# battery_monitor_6803-2_Rev6.net
KiCad netlist of a schematic drawn in EAGLE
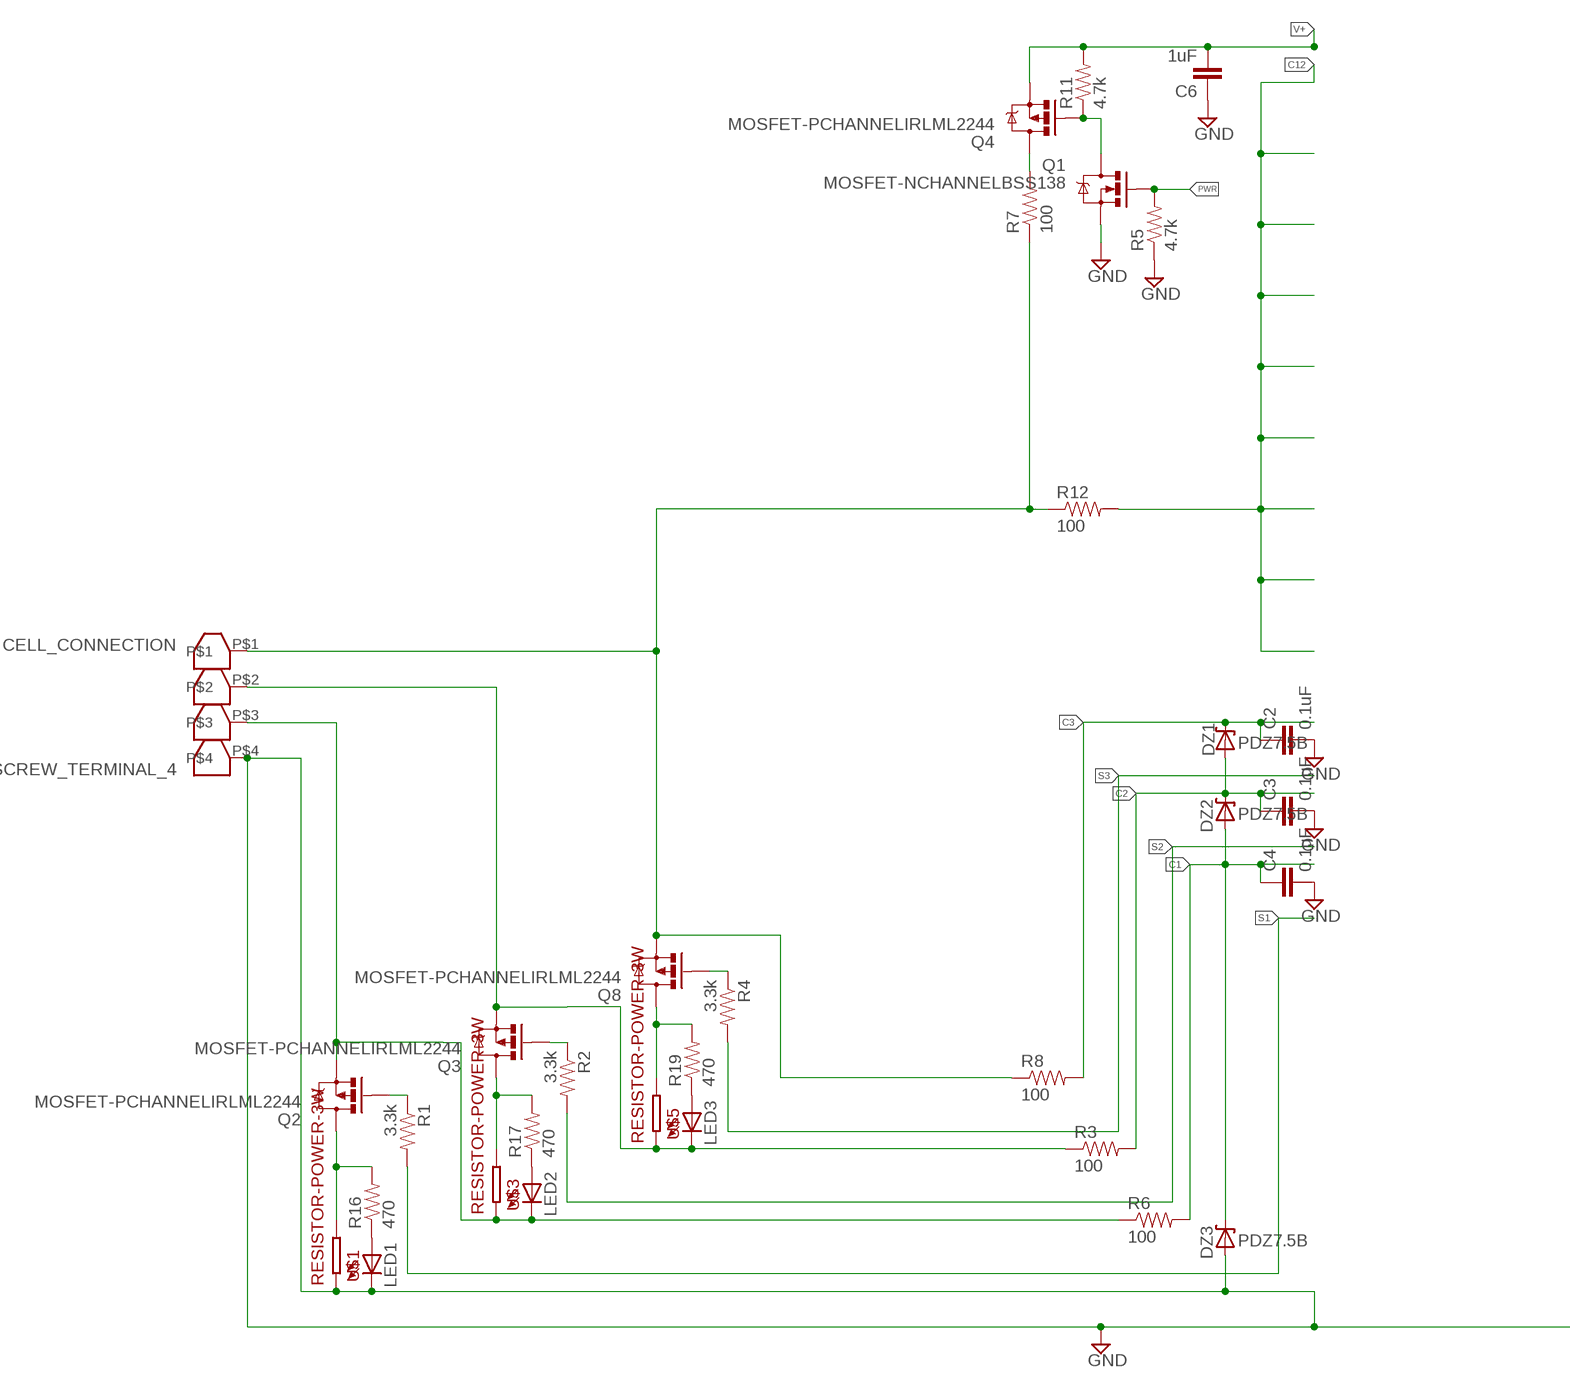
[diagram p0: schematic, sheet 1, part 1 of 2]
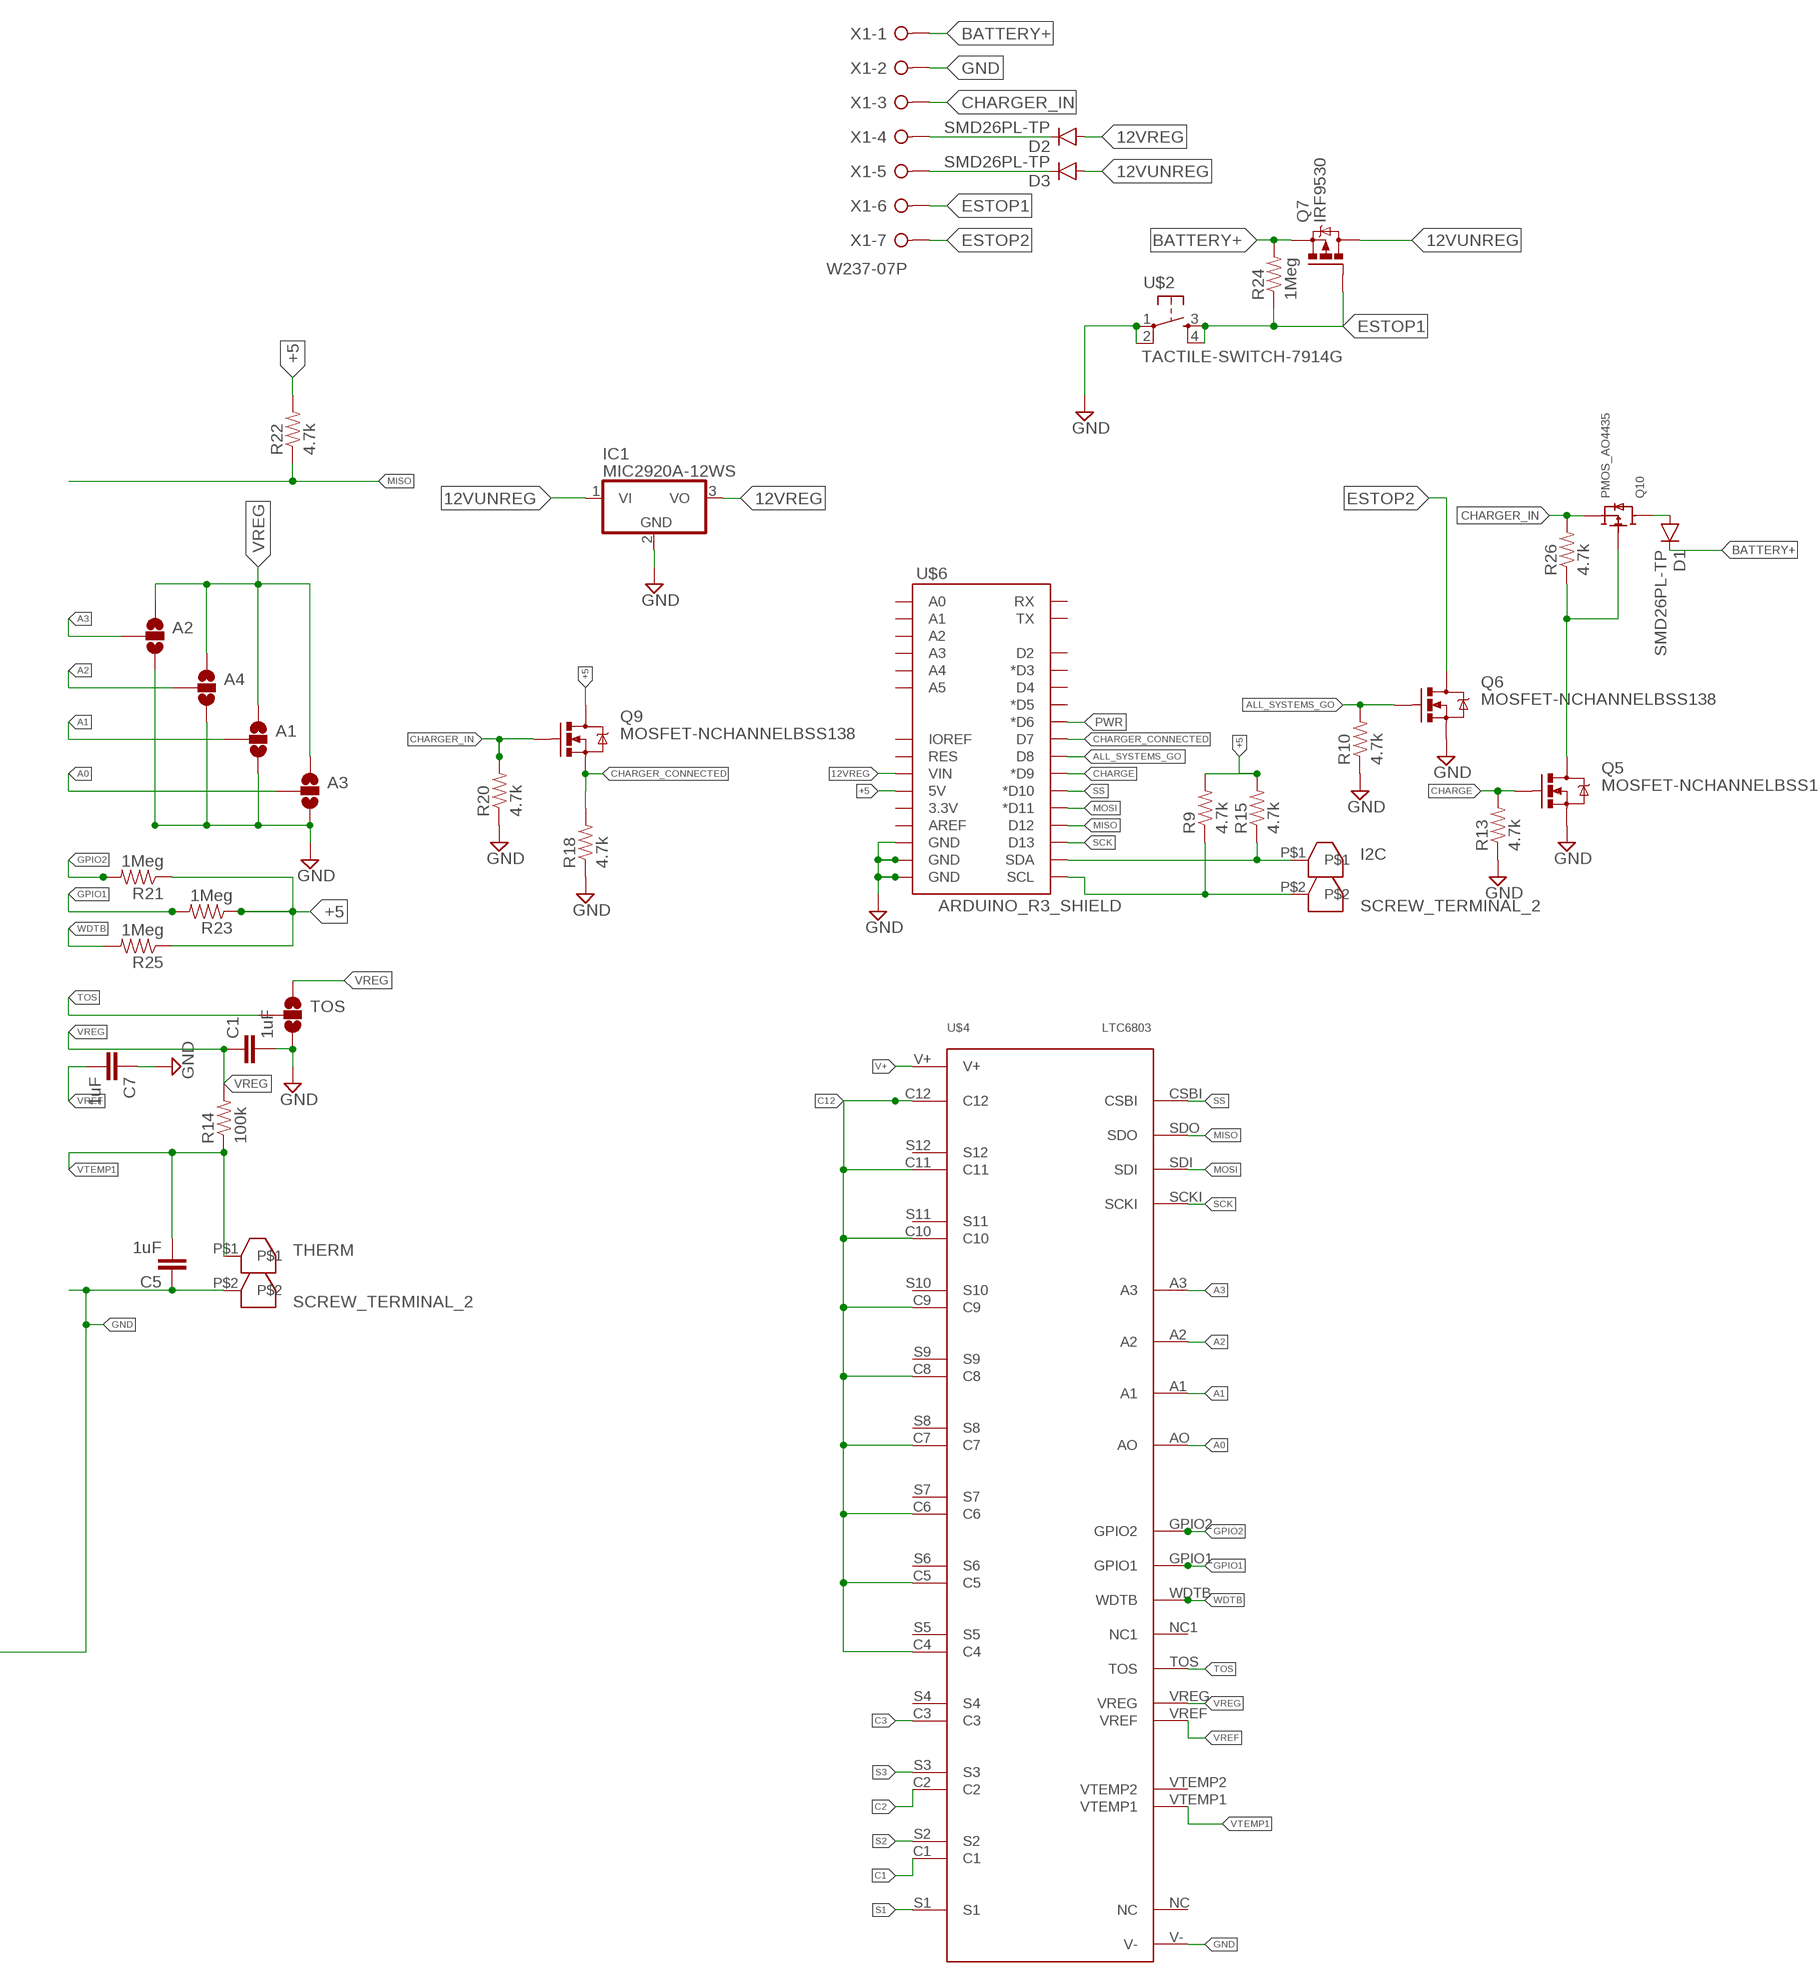
[diagram p1: schematic, sheet 1, part 2 of 2]

(export (version "E")
  (design (tool "Eeschema 10.0.6"))
  (components
    (comp (ref "A1")
      (value "SOLDERJUMPER_2WAYS")
      (footprint "eagle-import:SJ_3")
      (libsource (lib "eagle-import") (part "SOLDERJUMPER_2WAYS"))
    )
    (comp (ref "A2")
      (value "SOLDERJUMPER_2WAYS")
      (footprint "eagle-import:SJ_3")
      (libsource (lib "eagle-import") (part "SOLDERJUMPER_2WAYS"))
    )
    (comp (ref "A3")
      (value "SOLDERJUMPER_2WAYS")
      (footprint "eagle-import:SJ_3")
      (libsource (lib "eagle-import") (part "SOLDERJUMPER_2WAYS"))
    )
    (comp (ref "A4")
      (value "SOLDERJUMPER_2WAYS")
      (footprint "eagle-import:SJ_3")
      (libsource (lib "eagle-import") (part "SOLDERJUMPER_2WAYS"))
    )
    (comp (ref "C1")
      (value "1uF")
      (footprint "eagle-import:0603-CAP")
      (fields (field (name "MPN") "C0603X5R0J105M030BC") (field (name "PROD_ID") "CAP-08390"))
      (libsource (lib "eagle-import") (part "0.1UF-100V-10%(0603)"))
    )
    (comp (ref "C2")
      (value "0.1uF")
      (footprint "eagle-import:0603-CAP")
      (fields (field (name "MF") "AVX CORPORATION") (field (name "MPN") "0603YG104ZAT2A"))
      (libsource (lib "eagle-import") (part "0.1UF-100V-10%(0603)"))
    )
    (comp (ref "C3")
      (value "0.1uF")
      (footprint "eagle-import:0603-CAP")
      (fields (field (name "MF") "AVX CORPORATION") (field (name "MPN") "0603YG104ZAT2A"))
      (libsource (lib "eagle-import") (part "0.1UF-100V-10%(0603)"))
    )
    (comp (ref "C4")
      (value "0.1uF")
      (footprint "eagle-import:0603-CAP")
      (fields (field (name "MF") "AVX CORPORATION") (field (name "MPN") "0603YG104ZAT2A"))
      (libsource (lib "eagle-import") (part "0.1UF-100V-10%(0603)"))
    )
    (comp (ref "C5")
      (value "1uF")
      (footprint "eagle-import:0603-CAP")
      (fields (field (name "MPN") "C0603X5R0J105M030BC") (field (name "PROD_ID") "CAP-08390"))
      (libsource (lib "eagle-import") (part "0.1UF-100V-10%(0603)"))
    )
    (comp (ref "C6")
      (value "1uF")
      (footprint "eagle-import:0603-CAP")
      (fields (field (name "MPN") "C0603X5R0J105M030BC") (field (name "PROD_ID") "CAP-08390"))
      (libsource (lib "eagle-import") (part "0.1UF-100V-10%(0603)"))
    )
    (comp (ref "C7")
      (value "1uF")
      (footprint "eagle-import:0603-CAP")
      (fields (field (name "MPN") "C0603X5R0J105M030BC") (field (name "PROD_ID") "CAP-08390"))
      (libsource (lib "eagle-import") (part "0.1UF-100V-10%(0603)"))
    )
    (comp (ref "CELL_CONNECTION")
      (value "SCREW_TERMINAL_4")
      (footprint "eagle-import:SCREW_TERMINAL_4")
      (fields (field (name "MF") "TYCO ELECTRONICS") (field (name "MPN") "282834-4"))
      (libsource (lib "eagle-import") (part "SCREW_TERMINAL_4"))
    )
    (comp (ref "D1")
      (value "SMD26PL-TP")
      (footprint "eagle-import:SOD-123")
      (libsource (lib "eagle-import") (part "DIODESOD123"))
    )
    (comp (ref "D2")
      (value "SMD26PL-TP")
      (footprint "eagle-import:SOD-123")
      (libsource (lib "eagle-import") (part "DIODESOD123"))
    )
    (comp (ref "D3")
      (value "SMD26PL-TP")
      (footprint "eagle-import:SOD-123")
      (libsource (lib "eagle-import") (part "DIODESOD123"))
    )
    (comp (ref "DZ1")
      (value "PDZ7.5B")
      (footprint "eagle-import:SOD-323@1")
      (fields (field (name "MPN") "PDZ7.5B,115"))
      (libsource (lib "eagle-import") (part "DIODE-ZENER-BZT52"))
    )
    (comp (ref "DZ2")
      (value "PDZ7.5B")
      (footprint "eagle-import:SOD-323@1")
      (fields (field (name "MPN") "PDZ7.5B,115"))
      (libsource (lib "eagle-import") (part "DIODE-ZENER-BZT52"))
    )
    (comp (ref "DZ3")
      (value "PDZ7.5B")
      (footprint "eagle-import:SOD-323@1")
      (fields (field (name "MPN") "PDZ7.5B,115"))
      (libsource (lib "eagle-import") (part "DIODE-ZENER-BZT52"))
    )
    (comp (ref "I2C")
      (value "SCREW_TERMINAL_2")
      (footprint "eagle-import:SCREW_TERMINAL_2")
      (fields (field (name "MF") "TYCO ELECTRONICS") (field (name "MPN") "282834-2"))
      (libsource (lib "eagle-import") (part "SCREW_TERMINAL_2"))
    )
    (comp (ref "IC1")
      (value "MIC2920A-12WS")
      (footprint "eagle-import:SOT223")
      (libsource (lib "eagle-import") (part "MCP1703DB"))
    )
    (comp (ref "LED1")
      (value "LED0603")
      (footprint "eagle-import:LED-0603")
      (fields (field (name "MPN") "150060RS75000"))
      (libsource (lib "eagle-import") (part "LED0603"))
    )
    (comp (ref "LED2")
      (value "LED0603")
      (footprint "eagle-import:LED-0603")
      (fields (field (name "MPN") "150060RS75000"))
      (libsource (lib "eagle-import") (part "LED0603"))
    )
    (comp (ref "LED3")
      (value "LED0603")
      (footprint "eagle-import:LED-0603")
      (fields (field (name "MPN") "150060RS75000"))
      (libsource (lib "eagle-import") (part "LED0603"))
    )
    (comp (ref "Q1")
      (value "MOSFET-NCHANNELBSS138")
      (footprint "eagle-import:SOT23")
      (fields (field (name "MPN") "IRLML0030TRPBF"))
      (libsource (lib "eagle-import") (part "MOSFET-NCHANNELBSS138"))
    )
    (comp (ref "Q2")
      (value "MOSFET-PCHANNELIRLML2244")
      (footprint "eagle-import:SOT23-3@1")
      (fields (field (name "MPN") "IRLML2244TRPBF"))
      (libsource (lib "eagle-import") (part "MOSFET-PCHANNELIRLML2244"))
    )
    (comp (ref "Q3")
      (value "MOSFET-PCHANNELIRLML2244")
      (footprint "eagle-import:SOT23-3@1")
      (fields (field (name "MPN") "IRLML2244TRPBF"))
      (libsource (lib "eagle-import") (part "MOSFET-PCHANNELIRLML2244"))
    )
    (comp (ref "Q4")
      (value "MOSFET-PCHANNELIRLML2244")
      (footprint "eagle-import:SOT23-3@1")
      (fields (field (name "MPN") "IRLML2244TRPBF"))
      (libsource (lib "eagle-import") (part "MOSFET-PCHANNELIRLML2244"))
    )
    (comp (ref "Q5")
      (value "MOSFET-NCHANNELBSS138")
      (footprint "eagle-import:SOT23")
      (fields (field (name "MPN") "IRLML0030TRPBF"))
      (libsource (lib "eagle-import") (part "MOSFET-NCHANNELBSS138"))
    )
    (comp (ref "Q6")
      (value "MOSFET-NCHANNELBSS138")
      (footprint "eagle-import:SOT23")
      (fields (field (name "MPN") "IRLML0030TRPBF"))
      (libsource (lib "eagle-import") (part "MOSFET-NCHANNELBSS138"))
    )
    (comp (ref "Q7")
      (value "IRF9530")
      (footprint "eagle-import:TO220BV")
      (fields (field (name "MPN") "NTE2383"))
      (libsource (lib "eagle-import") (part "IRF9530"))
    )
    (comp (ref "Q8")
      (value "MOSFET-PCHANNELIRLML2244")
      (footprint "eagle-import:SOT23-3@1")
      (fields (field (name "MPN") "IRLML2244TRPBF"))
      (libsource (lib "eagle-import") (part "MOSFET-PCHANNELIRLML2244"))
    )
    (comp (ref "Q9")
      (value "MOSFET-NCHANNELBSS138")
      (footprint "eagle-import:SOT23")
      (fields (field (name "MPN") "IRLML0030TRPBF") (field (name "PROD_ID") "TRANS-00830"))
      (libsource (lib "eagle-import") (part "MOSFET-NCHANNELBSS138"))
    )
    (comp (ref "Q10")
      (value "PMOS_AO4435")
      (footprint "eagle-import:SOIC8")
      (fields (field (name "MPN") "SI9407BDY-T1-GE3"))
      (libsource (lib "eagle-import") (part "PMOS_AO4435"))
    )
    (comp (ref "R1")
      (value "3.3k")
      (footprint "eagle-import:0603-RES")
      (fields (field (name "MF") "VISHAY/DALE") (field (name "MPN") "CRCW06033K00FKEA"))
      (libsource (lib "eagle-import") (part "3.3KOHM1/10W1%(0603)"))
    )
    (comp (ref "R2")
      (value "3.3k")
      (footprint "eagle-import:0603-RES")
      (fields (field (name "MF") "VISHAY/DALE") (field (name "MPN") "CRCW06033K00FKEA"))
      (libsource (lib "eagle-import") (part "3.3KOHM1/10W1%(0603)"))
    )
    (comp (ref "R3")
      (value "100")
      (footprint "eagle-import:0603-RES")
      (fields (field (name "MPN") "ERJ-1GNF1000C"))
      (libsource (lib "eagle-import") (part "3.3KOHM1/10W1%(0603)"))
    )
    (comp (ref "R4")
      (value "3.3k")
      (footprint "eagle-import:0603-RES")
      (fields (field (name "MF") "VISHAY/DALE") (field (name "MPN") "CRCW06033K00FKEA"))
      (libsource (lib "eagle-import") (part "3.3KOHM1/10W1%(0603)"))
    )
    (comp (ref "R5")
      (value "4.7k")
      (footprint "eagle-import:0603-RES")
      (fields (field (name "MF") "VISHAY/DALE") (field (name "MPN") "CRCW06034K70FKEA"))
      (libsource (lib "eagle-import") (part "3.3KOHM1/10W1%(0603)"))
    )
    (comp (ref "R6")
      (value "100")
      (footprint "eagle-import:0603-RES")
      (fields (field (name "MPN") "ERJ-1GNF1000C"))
      (libsource (lib "eagle-import") (part "3.3KOHM1/10W1%(0603)"))
    )
    (comp (ref "R7")
      (value "100")
      (footprint "eagle-import:0603-RES")
      (fields (field (name "MPN") "ERJ-1GNF1000C"))
      (libsource (lib "eagle-import") (part "3.3KOHM1/10W1%(0603)"))
    )
    (comp (ref "R8")
      (value "100")
      (footprint "eagle-import:0603-RES")
      (fields (field (name "MPN") "ERJ-1GNF1000C"))
      (libsource (lib "eagle-import") (part "3.3KOHM1/10W1%(0603)"))
    )
    (comp (ref "R9")
      (value "4.7k")
      (footprint "eagle-import:0603-RES")
      (fields (field (name "MF") "VISHAY/DALE") (field (name "MPN") "CRCW06034K70FKEA"))
      (libsource (lib "eagle-import") (part "3.3KOHM1/10W1%(0603)"))
    )
    (comp (ref "R10")
      (value "4.7k")
      (footprint "eagle-import:0603-RES")
      (fields (field (name "MF") "VISHAY/DALE") (field (name "MPN") "CRCW06034K70FKEA"))
      (libsource (lib "eagle-import") (part "3.3KOHM1/10W1%(0603)"))
    )
    (comp (ref "R11")
      (value "4.7k")
      (footprint "eagle-import:0603-RES")
      (fields (field (name "MF") "VISHAY/DALE") (field (name "MPN") "CRCW06034K70FKEA"))
      (libsource (lib "eagle-import") (part "3.3KOHM1/10W1%(0603)"))
    )
    (comp (ref "R12")
      (value "100")
      (footprint "eagle-import:0603-RES")
      (fields (field (name "MPN") "ERJ-1GNF1000C"))
      (libsource (lib "eagle-import") (part "3.3KOHM1/10W1%(0603)"))
    )
    (comp (ref "R13")
      (value "4.7k")
      (footprint "eagle-import:0603-RES")
      (fields (field (name "MF") "VISHAY/DALE") (field (name "MPN") "CRCW06034K70FKEA"))
      (libsource (lib "eagle-import") (part "3.3KOHM1/10W1%(0603)"))
    )
    (comp (ref "R14")
      (value "100k")
      (footprint "eagle-import:0603-RES")
      (fields (field (name "MF") "FARNELL") (field (name "MPN") "MC0063W06035100K"))
      (libsource (lib "eagle-import") (part "3.3KOHM1/10W1%(0603)"))
    )
    (comp (ref "R15")
      (value "4.7k")
      (footprint "eagle-import:0603-RES")
      (fields (field (name "MF") "VISHAY/DALE") (field (name "MPN") "CRCW06034K70FKEA"))
      (libsource (lib "eagle-import") (part "3.3KOHM1/10W1%(0603)"))
    )
    (comp (ref "R16")
      (value "470")
      (footprint "eagle-import:0603-RES")
      (fields (field (name "MPN") "ERJ-P03F4700V") (field (name "PROD_ID") "RES-07851"))
      (libsource (lib "eagle-import") (part "3.3KOHM1/10W1%(0603)"))
    )
    (comp (ref "R17")
      (value "470")
      (footprint "eagle-import:0603-RES")
      (fields (field (name "MPN") "ERJ-P03F4700V") (field (name "PROD_ID") "RES-07851"))
      (libsource (lib "eagle-import") (part "3.3KOHM1/10W1%(0603)"))
    )
    (comp (ref "R18")
      (value "4.7k")
      (footprint "eagle-import:0603-RES")
      (fields
        (field (name "MF") "VISHAY/DALE")
        (field (name "MPN") "CRCW06034K70FKEA")
        (field (name "PROD_ID") "RES-07851")
      )
      (libsource (lib "eagle-import") (part "3.3KOHM1/10W1%(0603)"))
    )
    (comp (ref "R19")
      (value "470")
      (footprint "eagle-import:0603-RES")
      (fields (field (name "MPN") "ERJ-P03F4700V") (field (name "PROD_ID") "RES-07851"))
      (libsource (lib "eagle-import") (part "3.3KOHM1/10W1%(0603)"))
    )
    (comp (ref "R20")
      (value "4.7k")
      (footprint "eagle-import:0603-RES")
      (fields
        (field (name "MF") "VISHAY/DALE")
        (field (name "MPN") "CRCW06034K70FKEA")
        (field (name "PROD_ID") "RES-07851")
      )
      (libsource (lib "eagle-import") (part "3.3KOHM1/10W1%(0603)"))
    )
    (comp (ref "R21")
      (value "1Meg")
      (footprint "eagle-import:0603-RES")
      (fields (field (name "MPN") "ERJ-3EKF1004V") (field (name "PROD_ID") "RES-07851"))
      (libsource (lib "eagle-import") (part "3.3KOHM1/10W1%(0603)"))
    )
    (comp (ref "R22")
      (value "4.7k")
      (footprint "eagle-import:0603-RES")
      (fields
        (field (name "MF") "VISHAY/DALE")
        (field (name "MPN") "CRCW06034K70FKEA")
        (field (name "PROD_ID") "RES-07851")
      )
      (libsource (lib "eagle-import") (part "3.3KOHM1/10W1%(0603)"))
    )
    (comp (ref "R23")
      (value "1Meg")
      (footprint "eagle-import:0603-RES")
      (fields (field (name "MPN") "ERJ-3EKF1004V") (field (name "PROD_ID") "RES-07851"))
      (libsource (lib "eagle-import") (part "3.3KOHM1/10W1%(0603)"))
    )
    (comp (ref "R24")
      (value "1Meg")
      (footprint "eagle-import:0603-RES")
      (fields (field (name "MPN") "ERJ-3EKF1004V"))
      (libsource (lib "eagle-import") (part "3.3KOHM1/10W1%(0603)"))
    )
    (comp (ref "R25")
      (value "1Meg")
      (footprint "eagle-import:0603-RES")
      (fields (field (name "MPN") "ERJ-3EKF1004V") (field (name "PROD_ID") "RES-07851"))
      (libsource (lib "eagle-import") (part "3.3KOHM1/10W1%(0603)"))
    )
    (comp (ref "R26")
      (value "4.7k")
      (footprint "eagle-import:0603-RES")
      (fields
        (field (name "MF") "VISHAY/DALE")
        (field (name "MPN") "CRCW06034K70FKEA")
        (field (name "PROD_ID") "RES-07851")
      )
      (libsource (lib "eagle-import") (part "3.3KOHM1/10W1%(0603)"))
    )
    (comp (ref "THERM")
      (value "SCREW_TERMINAL_2")
      (footprint "eagle-import:SCREW_TERMINAL_2")
      (fields (field (name "MF") "TYCO ELECTRONICS") (field (name "MPN") "282834-2"))
      (libsource (lib "eagle-import") (part "SCREW_TERMINAL_2"))
    )
    (comp (ref "TOS")
      (value "SOLDERJUMPER_2WAYS")
      (footprint "eagle-import:SJ_3")
      (libsource (lib "eagle-import") (part "SOLDERJUMPER_2WAYS"))
    )
    (comp (ref "U$1")
      (value "RESISTOR-POWER-3W")
      (footprint "eagle-import:RESISTOR-3W")
      (fields (field (name "MPN") "ERG-3SJ200"))
      (libsource (lib "eagle-import") (part "RESISTOR-POWER-3W"))
    )
    (comp (ref "U$2")
      (value "TACTILE-SWITCH-7914G")
      (footprint "eagle-import:7914G")
      (fields (field (name "MF") "BOURNS, INC.") (field (name "MPN") "7914G-1-000E"))
      (libsource (lib "eagle-import") (part "TACTILE-SWITCH-7914G"))
    )
    (comp (ref "U$3")
      (value "RESISTOR-POWER-3W")
      (footprint "eagle-import:RESISTOR-3W")
      (fields (field (name "MPN") "ERG-3SJ200"))
      (libsource (lib "eagle-import") (part "RESISTOR-POWER-3W"))
    )
    (comp (ref "U$4")
      (value "LTC6803")
      (footprint "eagle-import:LTC6803_BREAKOUT")
      (fields (field (name "MPN") "LTC6803IG-2#PBF"))
      (libsource (lib "eagle-import") (part "LTC6803_BREAKOUT"))
    )
    (comp (ref "U$5")
      (value "RESISTOR-POWER-3W")
      (footprint "eagle-import:RESISTOR-3W")
      (fields (field (name "MPN") "ERG-3SJ200"))
      (libsource (lib "eagle-import") (part "RESISTOR-POWER-3W"))
    )
    (comp (ref "U$6")
      (value "ARDUINO_R3_SHIELD")
      (footprint "eagle-import:UNO_R3_SHIELD")
      (libsource (lib "eagle-import") (part "ARDUINO_R3_SHIELD"))
    )
    (comp (ref "X1")
      (value "W237-07P")
      (footprint "eagle-import:W237-7P")
      (libsource (lib "eagle-import") (part "W237-07P"))
    )
  )
  (nets
    (net (code "1") (name "+5") (class "Default")
      (node (ref "Q9") (pin "3") (pinfunction "D_3") (pintype "passive"))
      (node (ref "R15") (pin "2") (pinfunction "2_2") (pintype "passive"))
      (node (ref "R21") (pin "1") (pinfunction "1_1") (pintype "passive"))
      (node (ref "R22") (pin "2") (pinfunction "2_2") (pintype "passive"))
      (node (ref "R23") (pin "1") (pinfunction "1_1") (pintype "passive"))
      (node (ref "R25") (pin "1") (pinfunction "1_1") (pintype "passive"))
      (node (ref "R9") (pin "2") (pinfunction "2_2") (pintype "passive"))
      (node (ref "U$6") (pin "5V") (pinfunction "5V_5V") (pintype "bidirectional"))
    )
    (net (code "2") (name "12VREG") (class "Default")
      (node (ref "D2") (pin "A") (pinfunction "A_A") (pintype "passive"))
      (node (ref "IC1") (pin "3") (pinfunction "VO_3") (pintype "passive"))
      (node (ref "U$6") (pin "VIN") (pinfunction "VIN_VIN") (pintype "bidirectional"))
    )
    (net (code "3") (name "12VUNREG") (class "Default")
      (node (ref "D3") (pin "A") (pinfunction "A_A") (pintype "passive"))
      (node (ref "IC1") (pin "1") (pinfunction "VI_1") (pintype "input"))
      (node (ref "Q7") (pin "D") (pinfunction "D_D") (pintype "passive"))
    )
    (net (code "4") (name "A0") (class "Default")
      (node (ref "A3") (pin "2") (pinfunction "2_2") (pintype "passive"))
      (node (ref "U$4") (pin "AO") (pinfunction "AO_AO") (pintype "bidirectional"))
    )
    (net (code "5") (name "A1") (class "Default")
      (node (ref "A1") (pin "2") (pinfunction "2_2") (pintype "passive"))
      (node (ref "U$4") (pin "A1") (pinfunction "A1_A1") (pintype "bidirectional"))
    )
    (net (code "6") (name "A2") (class "Default")
      (node (ref "A4") (pin "2") (pinfunction "2_2") (pintype "passive"))
      (node (ref "U$4") (pin "A2") (pinfunction "A2_A2") (pintype "bidirectional"))
    )
    (net (code "7") (name "A3") (class "Default")
      (node (ref "A2") (pin "2") (pinfunction "2_2") (pintype "passive"))
      (node (ref "U$4") (pin "A3") (pinfunction "A3_A3") (pintype "bidirectional"))
    )
    (net (code "8") (name "ALL_SYSTEMS_GO") (class "Default")
      (node (ref "Q6") (pin "1") (pinfunction "G_1") (pintype "passive"))
      (node (ref "R10") (pin "2") (pinfunction "2_2") (pintype "passive"))
      (node (ref "U$6") (pin "D8") (pinfunction "D8_D8") (pintype "bidirectional"))
    )
    (net (code "9") (name "BATTERY+") (class "Default")
      (node (ref "D1") (pin "C") (pinfunction "C_C") (pintype "passive"))
      (node (ref "Q7") (pin "S") (pinfunction "S_S") (pintype "passive"))
      (node (ref "R24") (pin "2") (pinfunction "2_2") (pintype "passive"))
      (node (ref "X1") (pin "1") (pinfunction "KL_1") (pintype "passive"))
    )
    (net (code "10") (name "C1") (class "Default")
      (node (ref "C4") (pin "1") (pinfunction "1_1") (pintype "passive"))
      (node (ref "DZ2") (pin "2") (pinfunction "A_2") (pintype "passive"))
      (node (ref "DZ3") (pin "1") (pinfunction "C_1") (pintype "passive"))
      (node (ref "R6") (pin "2") (pinfunction "2_2") (pintype "passive"))
      (node (ref "U$4") (pin "C1") (pinfunction "C1_C1") (pintype "bidirectional"))
    )
    (net (code "11") (name "C2") (class "Default")
      (node (ref "C3") (pin "1") (pinfunction "1_1") (pintype "passive"))
      (node (ref "DZ1") (pin "2") (pinfunction "A_2") (pintype "passive"))
      (node (ref "DZ2") (pin "1") (pinfunction "C_1") (pintype "passive"))
      (node (ref "R3") (pin "2") (pinfunction "2_2") (pintype "passive"))
      (node (ref "U$4") (pin "C2") (pinfunction "C2_C2") (pintype "bidirectional"))
    )
    (net (code "12") (name "C3") (class "Default")
      (node (ref "C2") (pin "1") (pinfunction "1_1") (pintype "passive"))
      (node (ref "DZ1") (pin "1") (pinfunction "C_1") (pintype "passive"))
      (node (ref "R8") (pin "2") (pinfunction "2_2") (pintype "passive"))
      (node (ref "U$4") (pin "C3") (pinfunction "C3_C3") (pintype "bidirectional"))
    )
    (net (code "13") (name "C12") (class "Default")
      (node (ref "R12") (pin "2") (pinfunction "2_2") (pintype "passive"))
      (node (ref "U$4") (pin "C10") (pinfunction "C10_C10") (pintype "bidirectional"))
      (node (ref "U$4") (pin "C11") (pinfunction "C11_C11") (pintype "bidirectional"))
      (node (ref "U$4") (pin "C12") (pinfunction "C12_C12") (pintype "bidirectional"))
      (node (ref "U$4") (pin "C4") (pinfunction "C4_C4") (pintype "bidirectional"))
      (node (ref "U$4") (pin "C5") (pinfunction "C5_C5") (pintype "bidirectional"))
      (node (ref "U$4") (pin "C6") (pinfunction "C6_C6") (pintype "bidirectional"))
      (node (ref "U$4") (pin "C7") (pinfunction "C7_C7") (pintype "bidirectional"))
      (node (ref "U$4") (pin "C8") (pinfunction "C8_C8") (pintype "bidirectional"))
      (node (ref "U$4") (pin "C9") (pinfunction "C9_C9") (pintype "bidirectional"))
    )
    (net (code "14") (name "CHARGE") (class "Default")
      (node (ref "Q5") (pin "1") (pinfunction "G_1") (pintype "passive"))
      (node (ref "R13") (pin "2") (pinfunction "2_2") (pintype "passive"))
      (node (ref "U$6") (pin "D9") (pinfunction "*D9_D9") (pintype "bidirectional"))
    )
    (net (code "15") (name "CHARGER_CONNECTED") (class "Default")
      (node (ref "Q9") (pin "2") (pinfunction "S_2") (pintype "passive"))
      (node (ref "R18") (pin "2") (pinfunction "2_2") (pintype "passive"))
      (node (ref "U$6") (pin "D7") (pinfunction "D7_D7") (pintype "bidirectional"))
    )
    (net (code "16") (name "CHARGER_IN") (class "Default")
      (node (ref "Q10") (pin "1") (pinfunction "SOURCE_1") (pintype "bidirectional"))
      (node (ref "Q10") (pin "2") (pinfunction "SOURCE_2") (pintype "bidirectional"))
      (node (ref "Q10") (pin "3") (pinfunction "SOURCE_3") (pintype "bidirectional"))
      (node (ref "Q9") (pin "1") (pinfunction "G_1") (pintype "passive"))
      (node (ref "R20") (pin "2") (pinfunction "2_2") (pintype "passive"))
      (node (ref "R26") (pin "2") (pinfunction "2_2") (pintype "passive"))
      (node (ref "X1") (pin "3") (pinfunction "KL_3") (pintype "passive"))
    )
    (net (code "17") (name "ESTOP1") (class "Default")
      (node (ref "Q7") (pin "G") (pinfunction "G_G") (pintype "passive"))
      (node (ref "R24") (pin "1") (pinfunction "1_1") (pintype "passive"))
      (node (ref "U$2") (pin "3") (pinfunction "3_3") (pintype "passive"))
      (node (ref "U$2") (pin "4") (pinfunction "4_4") (pintype "passive"))
      (node (ref "X1") (pin "6") (pinfunction "KL_6") (pintype "passive"))
    )
    (net (code "18") (name "ESTOP2") (class "Default")
      (node (ref "Q6") (pin "3") (pinfunction "D_3") (pintype "passive"))
      (node (ref "X1") (pin "7") (pinfunction "KL_7") (pintype "passive"))
    )
    (net (code "19") (name "GND") (class "Default")
      (node (ref "A1") (pin "3") (pinfunction "3_3") (pintype "passive"))
      (node (ref "A2") (pin "3") (pinfunction "3_3") (pintype "passive"))
      (node (ref "A3") (pin "3") (pinfunction "3_3") (pintype "passive"))
      (node (ref "A4") (pin "3") (pinfunction "3_3") (pintype "passive"))
      (node (ref "C1") (pin "2") (pinfunction "2_2") (pintype "passive"))
      (node (ref "C2") (pin "2") (pinfunction "2_2") (pintype "passive"))
      (node (ref "C3") (pin "2") (pinfunction "2_2") (pintype "passive"))
      (node (ref "C4") (pin "2") (pinfunction "2_2") (pintype "passive"))
      (node (ref "C5") (pin "1") (pinfunction "1_1") (pintype "passive"))
      (node (ref "C6") (pin "1") (pinfunction "1_1") (pintype "passive"))
      (node (ref "C7") (pin "1") (pinfunction "1_1") (pintype "passive"))
      (node (ref "CELL_CONNECTION") (pin "P$4") (pinfunction "P$4_P$4") (pintype "bidirectional"))
      (node (ref "DZ3") (pin "2") (pinfunction "A_2") (pintype "passive"))
      (node (ref "IC1") (pin "2") (pinfunction "GND_2") (pintype "passive"))
      (node (ref "LED1") (pin "C") (pinfunction "C_C") (pintype "passive"))
      (node (ref "Q1") (pin "2") (pinfunction "S_2") (pintype "passive"))
      (node (ref "Q5") (pin "2") (pinfunction "S_2") (pintype "passive"))
      (node (ref "Q6") (pin "2") (pinfunction "S_2") (pintype "passive"))
      (node (ref "R10") (pin "1") (pinfunction "1_1") (pintype "passive"))
      (node (ref "R13") (pin "1") (pinfunction "1_1") (pintype "passive"))
      (node (ref "R18") (pin "1") (pinfunction "1_1") (pintype "passive"))
      (node (ref "R20") (pin "1") (pinfunction "1_1") (pintype "passive"))
      (node (ref "R5") (pin "1") (pinfunction "1_1") (pintype "passive"))
      (node (ref "THERM") (pin "P$2") (pinfunction "P$2_P$2") (pintype "bidirectional"))
      (node (ref "TOS") (pin "3") (pinfunction "3_3") (pintype "passive"))
      (node (ref "U$1") (pin "P$2") (pinfunction "P$2_P$2") (pintype "bidirectional"))
      (node (ref "U$2") (pin "1") (pinfunction "1_1") (pintype "passive"))
      (node (ref "U$2") (pin "2") (pinfunction "2_2") (pintype "passive"))
      (node (ref "U$4") (pin "V-") (pinfunction "V-_V-") (pintype "bidirectional"))
      (node (ref "U$6") (pin "GND@0") (pinfunction "GND_GND@0") (pintype "bidirectional"))
      (node (ref "U$6") (pin "GND@1") (pinfunction "GND_GND@1") (pintype "bidirectional"))
      (node (ref "U$6") (pin "GND@2") (pinfunction "GND_GND@2") (pintype "bidirectional"))
      (node (ref "X1") (pin "2") (pinfunction "KL_2") (pintype "passive"))
    )
    (net (code "20") (name "GPIO1") (class "Default")
      (node (ref "R23") (pin "2") (pinfunction "2_2") (pintype "passive"))
      (node (ref "U$4") (pin "GPIO1") (pinfunction "GPIO1_GPIO1") (pintype "bidirectional"))
    )
    (net (code "21") (name "GPIO2") (class "Default")
      (node (ref "R21") (pin "2") (pinfunction "2_2") (pintype "passive"))
      (node (ref "U$4") (pin "GPIO2") (pinfunction "GPIO2_GPIO2") (pintype "bidirectional"))
    )
    (net (code "22") (name "MISO") (class "Default")
      (node (ref "R22") (pin "1") (pinfunction "1_1") (pintype "passive"))
      (node (ref "U$4") (pin "SDO") (pinfunction "SDO_SDO") (pintype "bidirectional"))
      (node (ref "U$6") (pin "D12") (pinfunction "D12_D12") (pintype "bidirectional"))
    )
    (net (code "23") (name "MOSI") (class "Default")
      (node (ref "U$4") (pin "SDI") (pinfunction "SDI_SDI") (pintype "bidirectional"))
      (node (ref "U$6") (pin "D11") (pinfunction "*D11_D11") (pintype "bidirectional"))
    )
    (net (code "24") (name "Net-(D1-PadA)") (class "Default")
      (node (ref "D1") (pin "A") (pinfunction "A_A") (pintype "passive"))
      (node (ref "Q10") (pin "5") (pinfunction "DRAIN_5") (pintype "bidirectional"))
      (node (ref "Q10") (pin "6") (pinfunction "DRAIN_6") (pintype "bidirectional"))
      (node (ref "Q10") (pin "7") (pinfunction "DRAIN_7") (pintype "bidirectional"))
      (node (ref "Q10") (pin "8") (pinfunction "DRAIN_8") (pintype "bidirectional"))
    )
    (net (code "25") (name "Net-(I2C-PadP$1)") (class "Default")
      (node (ref "I2C") (pin "P$1") (pinfunction "P$1_P$1") (pintype "bidirectional"))
      (node (ref "R15") (pin "1") (pinfunction "1_1") (pintype "passive"))
      (node (ref "U$6") (pin "SDA") (pinfunction "SDA_SDA") (pintype "bidirectional"))
    )
    (net (code "26") (name "Net-(I2C-PadP$2)") (class "Default")
      (node (ref "I2C") (pin "P$2") (pinfunction "P$2_P$2") (pintype "bidirectional"))
      (node (ref "R9") (pin "1") (pinfunction "1_1") (pintype "passive"))
      (node (ref "U$6") (pin "SCL") (pinfunction "SCL_SCL") (pintype "bidirectional"))
    )
    (net (code "27") (name "Net-(LED1-PadA)") (class "Default")
      (node (ref "LED1") (pin "A") (pinfunction "A_A") (pintype "passive"))
      (node (ref "R16") (pin "1") (pinfunction "1_1") (pintype "passive"))
    )
    (net (code "28") (name "Net-(LED2-PadA)") (class "Default")
      (node (ref "LED2") (pin "A") (pinfunction "A_A") (pintype "passive"))
      (node (ref "R17") (pin "1") (pinfunction "1_1") (pintype "passive"))
    )
    (net (code "29") (name "Net-(LED3-PadA)") (class "Default")
      (node (ref "LED3") (pin "A") (pinfunction "A_A") (pintype "passive"))
      (node (ref "R19") (pin "1") (pinfunction "1_1") (pintype "passive"))
    )
    (net (code "30") (name "Net-(Q1-D)") (class "Default")
      (node (ref "Q1") (pin "3") (pinfunction "D_3") (pintype "passive"))
      (node (ref "Q4") (pin "1") (pinfunction "G_1") (pintype "passive"))
      (node (ref "R11") (pin "1") (pinfunction "1_1") (pintype "passive"))
    )
    (net (code "31") (name "Net-(Q2-D)") (class "Default")
      (node (ref "Q2") (pin "3") (pinfunction "D_3") (pintype "passive"))
      (node (ref "R16") (pin "2") (pinfunction "2_2") (pintype "passive"))
      (node (ref "U$1") (pin "P$1") (pinfunction "P$1_P$1") (pintype "bidirectional"))
    )
    (net (code "32") (name "Net-(Q2-G)") (class "Default")
      (node (ref "Q2") (pin "1") (pinfunction "G_1") (pintype "passive"))
      (node (ref "R1") (pin "1") (pinfunction "1_1") (pintype "passive"))
    )
    (net (code "33") (name "Net-(Q2-S)") (class "Default")
      (node (ref "CELL_CONNECTION") (pin "P$3") (pinfunction "P$3_P$3") (pintype "bidirectional"))
      (node (ref "LED2") (pin "C") (pinfunction "C_C") (pintype "passive"))
      (node (ref "Q2") (pin "2") (pinfunction "S_2") (pintype "passive"))
      (node (ref "R6") (pin "1") (pinfunction "1_1") (pintype "passive"))
      (node (ref "U$3") (pin "P$2") (pinfunction "P$2_P$2") (pintype "bidirectional"))
    )
    (net (code "34") (name "Net-(Q3-D)") (class "Default")
      (node (ref "Q3") (pin "3") (pinfunction "D_3") (pintype "passive"))
      (node (ref "R17") (pin "2") (pinfunction "2_2") (pintype "passive"))
      (node (ref "U$3") (pin "P$1") (pinfunction "P$1_P$1") (pintype "bidirectional"))
    )
    (net (code "35") (name "Net-(Q3-G)") (class "Default")
      (node (ref "Q3") (pin "1") (pinfunction "G_1") (pintype "passive"))
      (node (ref "R2") (pin "1") (pinfunction "1_1") (pintype "passive"))
    )
    (net (code "36") (name "Net-(Q3-S)") (class "Default")
      (node (ref "CELL_CONNECTION") (pin "P$2") (pinfunction "P$2_P$2") (pintype "bidirectional"))
      (node (ref "LED3") (pin "C") (pinfunction "C_C") (pintype "passive"))
      (node (ref "Q3") (pin "2") (pinfunction "S_2") (pintype "passive"))
      (node (ref "R3") (pin "1") (pinfunction "1_1") (pintype "passive"))
      (node (ref "U$5") (pin "P$2") (pinfunction "P$2_P$2") (pintype "bidirectional"))
    )
    (net (code "37") (name "Net-(Q4-D)") (class "Default")
      (node (ref "Q4") (pin "3") (pinfunction "D_3") (pintype "passive"))
      (node (ref "R7") (pin "2") (pinfunction "2_2") (pintype "passive"))
    )
    (net (code "38") (name "Net-(Q8-D)") (class "Default")
      (node (ref "Q8") (pin "3") (pinfunction "D_3") (pintype "passive"))
      (node (ref "R19") (pin "2") (pinfunction "2_2") (pintype "passive"))
      (node (ref "U$5") (pin "P$1") (pinfunction "P$1_P$1") (pintype "bidirectional"))
    )
    (net (code "39") (name "Net-(Q8-G)") (class "Default")
      (node (ref "Q8") (pin "1") (pinfunction "G_1") (pintype "passive"))
      (node (ref "R4") (pin "1") (pinfunction "1_1") (pintype "passive"))
    )
    (net (code "40") (name "Net-(Q8-S)") (class "Default")
      (node (ref "CELL_CONNECTION") (pin "P$1") (pinfunction "P$1_P$1") (pintype "bidirectional"))
      (node (ref "Q8") (pin "2") (pinfunction "S_2") (pintype "passive"))
      (node (ref "R12") (pin "1") (pinfunction "1_1") (pintype "passive"))
      (node (ref "R7") (pin "1") (pinfunction "1_1") (pintype "passive"))
      (node (ref "R8") (pin "1") (pinfunction "1_1") (pintype "passive"))
    )
    (net (code "41") (name "Net-(Q10-GATE)") (class "Default")
      (node (ref "Q10") (pin "4") (pinfunction "GATE_4") (pintype "bidirectional"))
      (node (ref "Q5") (pin "3") (pinfunction "D_3") (pintype "passive"))
      (node (ref "R26") (pin "1") (pinfunction "1_1") (pintype "passive"))
    )
    (net (code "42") (name "Net-(X1D-KL)") (class "Default")
      (node (ref "D2") (pin "C") (pinfunction "C_C") (pintype "passive"))
      (node (ref "X1") (pin "4") (pinfunction "KL_4") (pintype "passive"))
    )
    (net (code "43") (name "Net-(X1E-KL)") (class "Default")
      (node (ref "D3") (pin "C") (pinfunction "C_C") (pintype "passive"))
      (node (ref "X1") (pin "5") (pinfunction "KL_5") (pintype "passive"))
    )
    (net (code "44") (name "PWR") (class "Default")
      (node (ref "Q1") (pin "1") (pinfunction "G_1") (pintype "passive"))
      (node (ref "R5") (pin "2") (pinfunction "2_2") (pintype "passive"))
      (node (ref "U$6") (pin "D6") (pinfunction "*D6_D6") (pintype "bidirectional"))
    )
    (net (code "45") (name "S1") (class "Default")
      (node (ref "R1") (pin "2") (pinfunction "2_2") (pintype "passive"))
      (node (ref "U$4") (pin "S1") (pinfunction "S1_S1") (pintype "bidirectional"))
    )
    (net (code "46") (name "S2") (class "Default")
      (node (ref "R2") (pin "2") (pinfunction "2_2") (pintype "passive"))
      (node (ref "U$4") (pin "S2") (pinfunction "S2_S2") (pintype "bidirectional"))
    )
    (net (code "47") (name "S3") (class "Default")
      (node (ref "R4") (pin "2") (pinfunction "2_2") (pintype "passive"))
      (node (ref "U$4") (pin "S3") (pinfunction "S3_S3") (pintype "bidirectional"))
    )
    (net (code "48") (name "SCK") (class "Default")
      (node (ref "U$4") (pin "SCKI") (pinfunction "SCKI_SCKI") (pintype "bidirectional"))
      (node (ref "U$6") (pin "D13") (pinfunction "D13_D13") (pintype "bidirectional"))
    )
    (net (code "49") (name "SS") (class "Default")
      (node (ref "U$4") (pin "CSBI") (pinfunction "CSBI_CSBI") (pintype "bidirectional"))
      (node (ref "U$6") (pin "D10") (pinfunction "*D10_D10") (pintype "bidirectional"))
    )
    (net (code "50") (name "TOS") (class "Default")
      (node (ref "TOS") (pin "2") (pinfunction "2_2") (pintype "passive"))
      (node (ref "U$4") (pin "TOS") (pinfunction "TOS_TOS") (pintype "bidirectional"))
    )
    (net (code "51") (name "V+") (class "Default")
      (node (ref "C6") (pin "2") (pinfunction "2_2") (pintype "passive"))
      (node (ref "Q4") (pin "2") (pinfunction "S_2") (pintype "passive"))
      (node (ref "R11") (pin "2") (pinfunction "2_2") (pintype "passive"))
      (node (ref "U$4") (pin "V+") (pinfunction "V+_V+") (pintype "bidirectional"))
    )
    (net (code "52") (name "VREF") (class "Default")
      (node (ref "C7") (pin "2") (pinfunction "2_2") (pintype "passive"))
      (node (ref "U$4") (pin "VREF") (pinfunction "VREF_VREF") (pintype "bidirectional"))
    )
    (net (code "53") (name "VREG") (class "Default")
      (node (ref "A1") (pin "1") (pinfunction "1_1") (pintype "passive"))
      (node (ref "A2") (pin "1") (pinfunction "1_1") (pintype "passive"))
      (node (ref "A3") (pin "1") (pinfunction "1_1") (pintype "passive"))
      (node (ref "A4") (pin "1") (pinfunction "1_1") (pintype "passive"))
      (node (ref "C1") (pin "1") (pinfunction "1_1") (pintype "passive"))
      (node (ref "R14") (pin "2") (pinfunction "2_2") (pintype "passive"))
      (node (ref "TOS") (pin "1") (pinfunction "1_1") (pintype "passive"))
      (node (ref "U$4") (pin "VREG") (pinfunction "VREG_VREG") (pintype "bidirectional"))
    )
    (net (code "54") (name "VTEMP1") (class "Default")
      (node (ref "C5") (pin "2") (pinfunction "2_2") (pintype "passive"))
      (node (ref "R14") (pin "1") (pinfunction "1_1") (pintype "passive"))
      (node (ref "THERM") (pin "P$1") (pinfunction "P$1_P$1") (pintype "bidirectional"))
      (node (ref "U$4") (pin "VTEMP1") (pinfunction "VTEMP1_VTEMP1") (pintype "bidirectional"))
    )
    (net (code "55") (name "WDTB") (class "Default")
      (node (ref "R25") (pin "2") (pinfunction "2_2") (pintype "passive"))
      (node (ref "U$4") (pin "WDTB") (pinfunction "WDTB_WDTB") (pintype "bidirectional"))
    )
    (net (code "56") (name "unconnected-(U$4-PadNC)") (class "Default")
      (node (ref "U$4") (pin "NC") (pinfunction "NC_NC") (pintype "bidirectional"))
    )
    (net (code "57") (name "unconnected-(U$4-PadNC1)") (class "Default")
      (node (ref "U$4") (pin "NC1") (pinfunction "NC1_NC1") (pintype "bidirectional"))
    )
    (net (code "58") (name "unconnected-(U$4-PadS4)") (class "Default")
      (node (ref "U$4") (pin "S4") (pinfunction "S4_S4") (pintype "bidirectional"))
    )
    (net (code "59") (name "unconnected-(U$4-PadS5)") (class "Default")
      (node (ref "U$4") (pin "S5") (pinfunction "S5_S5") (pintype "bidirectional"))
    )
    (net (code "60") (name "unconnected-(U$4-PadS6)") (class "Default")
      (node (ref "U$4") (pin "S6") (pinfunction "S6_S6") (pintype "bidirectional"))
    )
    (net (code "61") (name "unconnected-(U$4-PadS7)") (class "Default")
      (node (ref "U$4") (pin "S7") (pinfunction "S7_S7") (pintype "bidirectional"))
    )
    (net (code "62") (name "unconnected-(U$4-PadS8)") (class "Default")
      (node (ref "U$4") (pin "S8") (pinfunction "S8_S8") (pintype "bidirectional"))
    )
    (net (code "63") (name "unconnected-(U$4-PadS9)") (class "Default")
      (node (ref "U$4") (pin "S9") (pinfunction "S9_S9") (pintype "bidirectional"))
    )
    (net (code "64") (name "unconnected-(U$4-PadS10)") (class "Default")
      (node (ref "U$4") (pin "S10") (pinfunction "S10_S10") (pintype "bidirectional"))
    )
    (net (code "65") (name "unconnected-(U$4-PadS11)") (class "Default")
      (node (ref "U$4") (pin "S11") (pinfunction "S11_S11") (pintype "bidirectional"))
    )
    (net (code "66") (name "unconnected-(U$4-PadS12)") (class "Default")
      (node (ref "U$4") (pin "S12") (pinfunction "S12_S12") (pintype "bidirectional"))
    )
    (net (code "67") (name "unconnected-(U$4-PadVTEMP2)") (class "Default")
      (node (ref "U$4") (pin "VTEMP2") (pinfunction "VTEMP2_VTEMP2") (pintype "bidirectional"))
    )
    (net (code "68") (name "unconnected-(U$6-*D3-PadD3)") (class "Default")
      (node (ref "U$6") (pin "D3") (pinfunction "*D3_D3") (pintype "bidirectional"))
    )
    (net (code "69") (name "unconnected-(U$6-*D5-PadD5)") (class "Default")
      (node (ref "U$6") (pin "D5") (pinfunction "*D5_D5") (pintype "bidirectional"))
    )
    (net (code "70") (name "unconnected-(U$6-Pad3.3V)") (class "Default")
      (node (ref "U$6") (pin "3.3V") (pinfunction "3.3V_3.3V") (pintype "bidirectional"))
    )
    (net (code "71") (name "unconnected-(U$6-PadA0)") (class "Default")
      (node (ref "U$6") (pin "A0") (pinfunction "A0_A0") (pintype "bidirectional"))
    )
    (net (code "72") (name "unconnected-(U$6-PadA1)") (class "Default")
      (node (ref "U$6") (pin "A1") (pinfunction "A1_A1") (pintype "bidirectional"))
    )
    (net (code "73") (name "unconnected-(U$6-PadA2)") (class "Default")
      (node (ref "U$6") (pin "A2") (pinfunction "A2_A2") (pintype "bidirectional"))
    )
    (net (code "74") (name "unconnected-(U$6-PadA3)") (class "Default")
      (node (ref "U$6") (pin "A3") (pinfunction "A3_A3") (pintype "bidirectional"))
    )
    (net (code "75") (name "unconnected-(U$6-PadA4)") (class "Default")
      (node (ref "U$6") (pin "A4") (pinfunction "A4_A4") (pintype "bidirectional"))
    )
    (net (code "76") (name "unconnected-(U$6-PadA5)") (class "Default")
      (node (ref "U$6") (pin "A5") (pinfunction "A5_A5") (pintype "bidirectional"))
    )
    (net (code "77") (name "unconnected-(U$6-PadAREF)") (class "Default")
      (node (ref "U$6") (pin "AREF") (pinfunction "AREF_AREF") (pintype "bidirectional"))
    )
    (net (code "78") (name "unconnected-(U$6-PadD2)") (class "Default")
      (node (ref "U$6") (pin "D2") (pinfunction "D2_D2") (pintype "bidirectional"))
    )
    (net (code "79") (name "unconnected-(U$6-PadD4)") (class "Default")
      (node (ref "U$6") (pin "D4") (pinfunction "D4_D4") (pintype "bidirectional"))
    )
    (net (code "80") (name "unconnected-(U$6-PadIOREF)") (class "Default")
      (node (ref "U$6") (pin "IOREF") (pinfunction "IOREF_IOREF") (pintype "bidirectional"))
    )
    (net (code "81") (name "unconnected-(U$6-PadRES)") (class "Default")
      (node (ref "U$6") (pin "RES") (pinfunction "RES_RES") (pintype "bidirectional"))
    )
    (net (code "82") (name "unconnected-(U$6-PadRX)") (class "Default")
      (node (ref "U$6") (pin "RX") (pinfunction "RX_RX") (pintype "bidirectional"))
    )
    (net (code "83") (name "unconnected-(U$6-PadTX)") (class "Default")
      (node (ref "U$6") (pin "TX") (pinfunction "TX_TX") (pintype "bidirectional"))
    )
  )
)
